# vrx.net
KiCad netlist of a schematic drawn in EAGLE
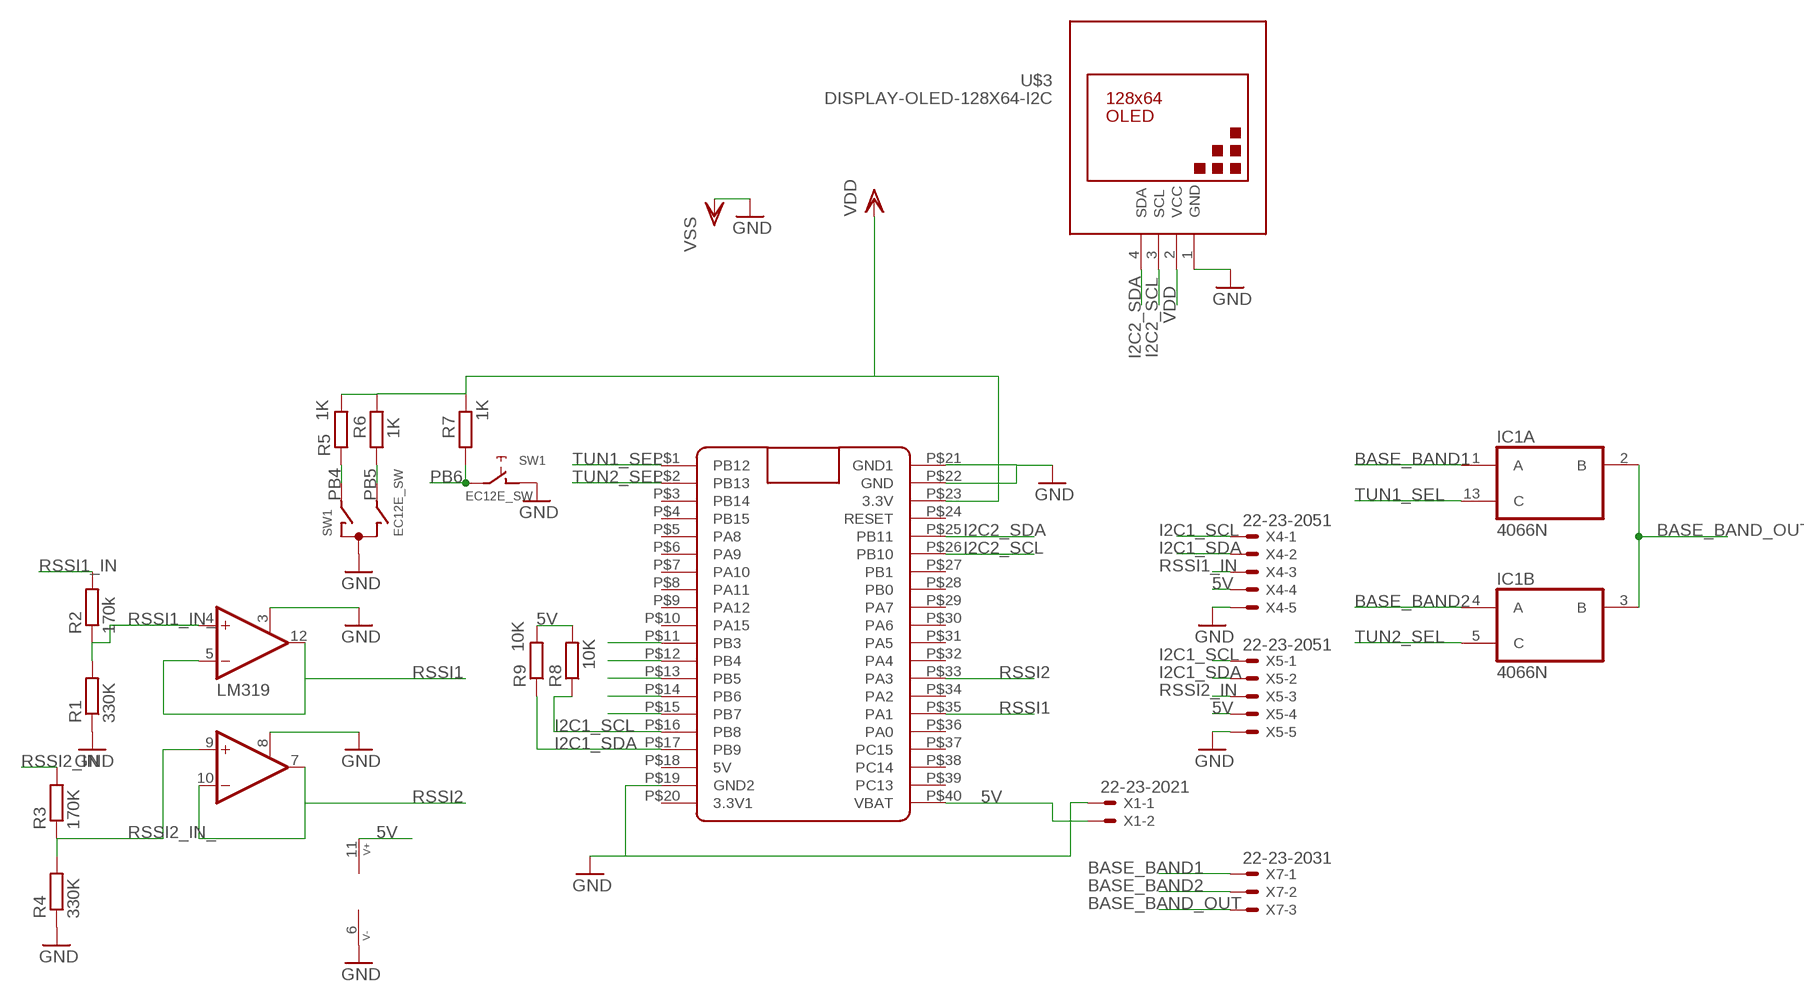
[diagram p0: schematic, sheet 1]

(export (version "E")
  (design (tool "Eeschema 10.0.6"))
  (components
    (comp (ref "IC1")
      (value "4066N")
      (footprint "eagle-import:DIL14")
      (libsource (lib "eagle-import") (part "4066N"))
    )
    (comp (ref "R1")
      (value "330K")
      (footprint "eagle-import:0204_7")
      (libsource (lib "eagle-import") (part "R-EU_0204/7"))
    )
    (comp (ref "R2")
      (value "170k")
      (footprint "eagle-import:0204_7")
      (libsource (lib "eagle-import") (part "R-EU_0204/7"))
    )
    (comp (ref "R3")
      (value "170K")
      (footprint "eagle-import:0204_7")
      (libsource (lib "eagle-import") (part "R-EU_0204/7"))
    )
    (comp (ref "R4")
      (value "330K")
      (footprint "eagle-import:0204_7")
      (libsource (lib "eagle-import") (part "R-EU_0204/7"))
    )
    (comp (ref "R5")
      (value "1K")
      (footprint "eagle-import:0204_7")
      (libsource (lib "eagle-import") (part "R-EU_0204/7"))
    )
    (comp (ref "R6")
      (value "1K")
      (footprint "eagle-import:0204_7")
      (libsource (lib "eagle-import") (part "R-EU_0204/7"))
    )
    (comp (ref "R7")
      (value "1K")
      (footprint "eagle-import:0204_7")
      (libsource (lib "eagle-import") (part "R-EU_0204/7"))
    )
    (comp (ref "R8")
      (value "10K")
      (footprint "eagle-import:0204_7")
      (libsource (lib "eagle-import") (part "R-EU_0204/7"))
    )
    (comp (ref "R9")
      (value "10K")
      (footprint "eagle-import:0204_7")
      (libsource (lib "eagle-import") (part "R-EU_0204/7"))
    )
    (comp (ref "SW1")
      (value "EC12E_SW")
      (footprint "eagle-import:ALPS_EC12E_SW")
      (fields (field (name "MPN") "EC12E2424407"))
      (libsource (lib "eagle-import") (part "EC12E_SW"))
    )
    (comp (ref "U$1")
      (value "BLUE_PILLADVANCED")
      (footprint "eagle-import:BLUE_PILL_ADV")
      (libsource (lib "eagle-import") (part "BLUE_PILLADVANCED"))
    )
    (comp (ref "U$2")
      (value "LM319")
      (footprint "eagle-import:DIL14")
      (libsource (lib "eagle-import") (part "LM319"))
    )
    (comp (ref "U$3")
      (value "DISPLAY-OLED-128X64-I2C")
      (footprint "eagle-import:DISPLAY-OLED-128X64-I2C")
      (libsource (lib "eagle-import") (part "DISPLAY-OLED-128X64-I2C"))
    )
    (comp (ref "X1")
      (value "22-23-2021")
      (footprint "eagle-import:22-23-2021")
      (fields (field (name "MF") "MOLEX"))
      (libsource (lib "eagle-import") (part "22-23-2021"))
    )
    (comp (ref "X4")
      (value "22-23-2051")
      (footprint "eagle-import:22-23-2051")
      (fields (field (name "MF") "MOLEX"))
      (libsource (lib "eagle-import") (part "22-23-2051"))
    )
    (comp (ref "X5")
      (value "22-23-2051")
      (footprint "eagle-import:22-23-2051")
      (fields (field (name "MF") "MOLEX"))
      (libsource (lib "eagle-import") (part "22-23-2051"))
    )
    (comp (ref "X7")
      (value "22-23-2031")
      (footprint "eagle-import:22-23-2031")
      (fields (field (name "MF") "MOLEX"))
      (libsource (lib "eagle-import") (part "22-23-2031"))
    )
  )
  (nets
    (net (code "1") (name "/5V") (class "Default")
      (node (ref "R8") (pin "2") (pinfunction "2_2") (pintype "passive"))
      (node (ref "R9") (pin "2") (pinfunction "2_2") (pintype "passive"))
      (node (ref "U$1") (pin "P$40") (pinfunction "VBAT_P$40") (pintype "bidirectional"))
      (node (ref "U$2") (pin "11") (pinfunction "V+_11") (pintype "power_in"))
      (node (ref "X1") (pin "2") (pinfunction "S_2") (pintype "passive"))
      (node (ref "X4") (pin "4") (pinfunction "S_4") (pintype "passive"))
      (node (ref "X5") (pin "4") (pinfunction "S_4") (pintype "passive"))
    )
    (net (code "2") (name "/BASE_BAND1") (class "Default")
      (node (ref "IC1") (pin "1") (pinfunction "A_1") (pintype "tri_state"))
      (node (ref "X7") (pin "1") (pinfunction "S_1") (pintype "passive"))
    )
    (net (code "3") (name "/BASE_BAND2") (class "Default")
      (node (ref "IC1") (pin "4") (pinfunction "A_4") (pintype "tri_state"))
      (node (ref "X7") (pin "2") (pinfunction "S_2") (pintype "passive"))
    )
    (net (code "4") (name "/BASE_BAND_OUT") (class "Default")
      (node (ref "IC1") (pin "2") (pinfunction "B_2") (pintype "tri_state"))
      (node (ref "IC1") (pin "3") (pinfunction "B_3") (pintype "tri_state"))
      (node (ref "X7") (pin "3") (pinfunction "S_3") (pintype "passive"))
    )
    (net (code "5") (name "/I2C1_SCL") (class "Default")
      (node (ref "R8") (pin "1") (pinfunction "1_1") (pintype "passive"))
      (node (ref "U$1") (pin "P$16") (pinfunction "PB8_P$16") (pintype "bidirectional"))
      (node (ref "X4") (pin "1") (pinfunction "S_1") (pintype "passive"))
      (node (ref "X5") (pin "1") (pinfunction "S_1") (pintype "passive"))
    )
    (net (code "6") (name "/I2C1_SDA") (class "Default")
      (node (ref "R9") (pin "1") (pinfunction "1_1") (pintype "passive"))
      (node (ref "U$1") (pin "P$17") (pinfunction "PB9_P$17") (pintype "bidirectional"))
      (node (ref "X4") (pin "2") (pinfunction "S_2") (pintype "passive"))
      (node (ref "X5") (pin "2") (pinfunction "S_2") (pintype "passive"))
    )
    (net (code "7") (name "/I2C2_SCL") (class "Default")
      (node (ref "U$1") (pin "P$26") (pinfunction "PB10_P$26") (pintype "bidirectional"))
      (node (ref "U$3") (pin "3") (pinfunction "SCL_3") (pintype "bidirectional"))
    )
    (net (code "8") (name "/I2C2_SDA") (class "Default")
      (node (ref "U$1") (pin "P$25") (pinfunction "PB11_P$25") (pintype "bidirectional"))
      (node (ref "U$3") (pin "4") (pinfunction "SDA_4") (pintype "bidirectional"))
    )
    (net (code "9") (name "/PB4") (class "Default")
      (node (ref "R5") (pin "1") (pinfunction "1_1") (pintype "passive"))
      (node (ref "SW1") (pin "A") (pinfunction "A_A") (pintype "passive"))
      (node (ref "U$1") (pin "P$12") (pinfunction "PB4_P$12") (pintype "bidirectional"))
    )
    (net (code "10") (name "/PB5") (class "Default")
      (node (ref "R6") (pin "1") (pinfunction "1_1") (pintype "passive"))
      (node (ref "SW1") (pin "B") (pinfunction "B_B") (pintype "passive"))
      (node (ref "U$1") (pin "P$13") (pinfunction "PB5_P$13") (pintype "bidirectional"))
    )
    (net (code "11") (name "/PB6") (class "Default")
      (node (ref "R7") (pin "1") (pinfunction "1_1") (pintype "passive"))
      (node (ref "SW1") (pin "E") (pinfunction "2_E") (pintype "passive"))
      (node (ref "U$1") (pin "P$14") (pinfunction "PB6_P$14") (pintype "bidirectional"))
    )
    (net (code "12") (name "/RSSI1") (class "Default")
      (node (ref "U$1") (pin "P$35") (pinfunction "PA1_P$35") (pintype "bidirectional"))
      (node (ref "U$2") (pin "12") (pinfunction "OUT_12") (pintype "output"))
      (node (ref "U$2") (pin "5") (pinfunction "-IN_5") (pintype "input"))
    )
    (net (code "13") (name "/RSSI1_IN") (class "Default")
      (node (ref "R2") (pin "2") (pinfunction "2_2") (pintype "passive"))
      (node (ref "X4") (pin "3") (pinfunction "S_3") (pintype "passive"))
    )
    (net (code "14") (name "/RSSI1_IN_") (class "Default")
      (node (ref "R1") (pin "2") (pinfunction "2_2") (pintype "passive"))
      (node (ref "R2") (pin "1") (pinfunction "1_1") (pintype "passive"))
      (node (ref "U$2") (pin "4") (pinfunction "+IN_4") (pintype "input"))
    )
    (net (code "15") (name "/RSSI2") (class "Default")
      (node (ref "U$1") (pin "P$33") (pinfunction "PA3_P$33") (pintype "bidirectional"))
      (node (ref "U$2") (pin "10") (pinfunction "-IN_10") (pintype "input"))
      (node (ref "U$2") (pin "7") (pinfunction "OUT_7") (pintype "output"))
    )
    (net (code "16") (name "/RSSI2_IN") (class "Default")
      (node (ref "R3") (pin "2") (pinfunction "2_2") (pintype "passive"))
      (node (ref "X5") (pin "3") (pinfunction "S_3") (pintype "passive"))
    )
    (net (code "17") (name "/RSSI2_IN_") (class "Default")
      (node (ref "R3") (pin "1") (pinfunction "1_1") (pintype "passive"))
      (node (ref "R4") (pin "2") (pinfunction "2_2") (pintype "passive"))
      (node (ref "U$2") (pin "9") (pinfunction "+IN_9") (pintype "input"))
    )
    (net (code "18") (name "/TUN1_SEL") (class "Default")
      (node (ref "IC1") (pin "13") (pinfunction "C_13") (pintype "input"))
      (node (ref "U$1") (pin "P$1") (pinfunction "PB12_P$1") (pintype "bidirectional"))
    )
    (net (code "19") (name "/TUN2_SEL") (class "Default")
      (node (ref "IC1") (pin "5") (pinfunction "C_5") (pintype "input"))
      (node (ref "U$1") (pin "P$2") (pinfunction "PB13_P$2") (pintype "bidirectional"))
    )
    (net (code "20") (name "GND") (class "Default")
      (node (ref "R1") (pin "1") (pinfunction "1_1") (pintype "passive"))
      (node (ref "R4") (pin "1") (pinfunction "1_1") (pintype "passive"))
      (node (ref "SW1") (pin "C") (pinfunction "C_C") (pintype "passive"))
      (node (ref "SW1") (pin "D") (pinfunction "1_D") (pintype "passive"))
      (node (ref "U$1") (pin "P$19") (pinfunction "GND2_P$19") (pintype "bidirectional"))
      (node (ref "U$1") (pin "P$21") (pinfunction "GND1_P$21") (pintype "power_in"))
      (node (ref "U$1") (pin "P$22") (pinfunction "GND_P$22") (pintype "bidirectional"))
      (node (ref "U$2") (pin "3") (pinfunction "SHDN_3") (pintype "passive"))
      (node (ref "U$2") (pin "6") (pinfunction "V-_6") (pintype "power_in"))
      (node (ref "U$2") (pin "8") (pinfunction "SHDN_8") (pintype "passive"))
      (node (ref "U$3") (pin "1") (pinfunction "GND_1") (pintype "power_in"))
      (node (ref "X1") (pin "1") (pinfunction "S_1") (pintype "passive"))
      (node (ref "X4") (pin "5") (pinfunction "S_5") (pintype "passive"))
      (node (ref "X5") (pin "5") (pinfunction "S_5") (pintype "passive"))
    )
    (net (code "21") (name "VDD") (class "Default")
      (node (ref "R5") (pin "2") (pinfunction "2_2") (pintype "passive"))
      (node (ref "R6") (pin "2") (pinfunction "2_2") (pintype "passive"))
      (node (ref "R7") (pin "2") (pinfunction "2_2") (pintype "passive"))
      (node (ref "U$1") (pin "P$23") (pinfunction "3.3V_P$23") (pintype "bidirectional"))
      (node (ref "U$3") (pin "2") (pinfunction "VCC_2") (pintype "power_in"))
    )
    (net (code "22") (name "unconnected-(U$1-3.3V1-PadP$20)") (class "Default")
      (node (ref "U$1") (pin "P$20") (pinfunction "3.3V1_P$20") (pintype "bidirectional"))
    )
    (net (code "23") (name "unconnected-(U$1-5V-PadP$18)") (class "Default")
      (node (ref "U$1") (pin "P$18") (pinfunction "5V_P$18") (pintype "bidirectional"))
    )
    (net (code "24") (name "unconnected-(U$1-PA0-PadP$36)") (class "Default")
      (node (ref "U$1") (pin "P$36") (pinfunction "PA0_P$36") (pintype "bidirectional"))
    )
    (net (code "25") (name "unconnected-(U$1-PA2-PadP$34)") (class "Default")
      (node (ref "U$1") (pin "P$34") (pinfunction "PA2_P$34") (pintype "bidirectional"))
    )
    (net (code "26") (name "unconnected-(U$1-PA4-PadP$32)") (class "Default")
      (node (ref "U$1") (pin "P$32") (pinfunction "PA4_P$32") (pintype "bidirectional"))
    )
    (net (code "27") (name "unconnected-(U$1-PA5-PadP$31)") (class "Default")
      (node (ref "U$1") (pin "P$31") (pinfunction "PA5_P$31") (pintype "bidirectional"))
    )
    (net (code "28") (name "unconnected-(U$1-PA6-PadP$30)") (class "Default")
      (node (ref "U$1") (pin "P$30") (pinfunction "PA6_P$30") (pintype "bidirectional"))
    )
    (net (code "29") (name "unconnected-(U$1-PA7-PadP$29)") (class "Default")
      (node (ref "U$1") (pin "P$29") (pinfunction "PA7_P$29") (pintype "bidirectional"))
    )
    (net (code "30") (name "unconnected-(U$1-PA8-PadP$5)") (class "Default")
      (node (ref "U$1") (pin "P$5") (pinfunction "PA8_P$5") (pintype "bidirectional"))
    )
    (net (code "31") (name "unconnected-(U$1-PA9-PadP$6)") (class "Default")
      (node (ref "U$1") (pin "P$6") (pinfunction "PA9_P$6") (pintype "bidirectional"))
    )
    (net (code "32") (name "unconnected-(U$1-PA10-PadP$7)") (class "Default")
      (node (ref "U$1") (pin "P$7") (pinfunction "PA10_P$7") (pintype "bidirectional"))
    )
    (net (code "33") (name "unconnected-(U$1-PA11-PadP$8)") (class "Default")
      (node (ref "U$1") (pin "P$8") (pinfunction "PA11_P$8") (pintype "bidirectional"))
    )
    (net (code "34") (name "unconnected-(U$1-PA12-PadP$9)") (class "Default")
      (node (ref "U$1") (pin "P$9") (pinfunction "PA12_P$9") (pintype "bidirectional"))
    )
    (net (code "35") (name "unconnected-(U$1-PA15-PadP$10)") (class "Default")
      (node (ref "U$1") (pin "P$10") (pinfunction "PA15_P$10") (pintype "bidirectional"))
    )
    (net (code "36") (name "unconnected-(U$1-PB0-PadP$28)") (class "Default")
      (node (ref "U$1") (pin "P$28") (pinfunction "PB0_P$28") (pintype "bidirectional"))
    )
    (net (code "37") (name "unconnected-(U$1-PB1-PadP$27)") (class "Default")
      (node (ref "U$1") (pin "P$27") (pinfunction "PB1_P$27") (pintype "bidirectional"))
    )
    (net (code "38") (name "unconnected-(U$1-PB3-PadP$11)") (class "Default")
      (node (ref "U$1") (pin "P$11") (pinfunction "PB3_P$11") (pintype "bidirectional"))
    )
    (net (code "39") (name "unconnected-(U$1-PB7-PadP$15)") (class "Default")
      (node (ref "U$1") (pin "P$15") (pinfunction "PB7_P$15") (pintype "bidirectional"))
    )
    (net (code "40") (name "unconnected-(U$1-PB14-PadP$3)") (class "Default")
      (node (ref "U$1") (pin "P$3") (pinfunction "PB14_P$3") (pintype "bidirectional"))
    )
    (net (code "41") (name "unconnected-(U$1-PB15-PadP$4)") (class "Default")
      (node (ref "U$1") (pin "P$4") (pinfunction "PB15_P$4") (pintype "bidirectional"))
    )
    (net (code "42") (name "unconnected-(U$1-PC13-PadP$39)") (class "Default")
      (node (ref "U$1") (pin "P$39") (pinfunction "PC13_P$39") (pintype "bidirectional"))
    )
    (net (code "43") (name "unconnected-(U$1-PC14-PadP$38)") (class "Default")
      (node (ref "U$1") (pin "P$38") (pinfunction "PC14_P$38") (pintype "bidirectional"))
    )
    (net (code "44") (name "unconnected-(U$1-PC15-PadP$37)") (class "Default")
      (node (ref "U$1") (pin "P$37") (pinfunction "PC15_P$37") (pintype "bidirectional"))
    )
    (net (code "45") (name "unconnected-(U$1-RESET-PadP$24)") (class "Default")
      (node (ref "U$1") (pin "P$24") (pinfunction "RESET_P$24") (pintype "bidirectional"))
    )
  )
)
